# DE-211024_1.net
KiCad netlist of a schematic drawn in Altium Designer
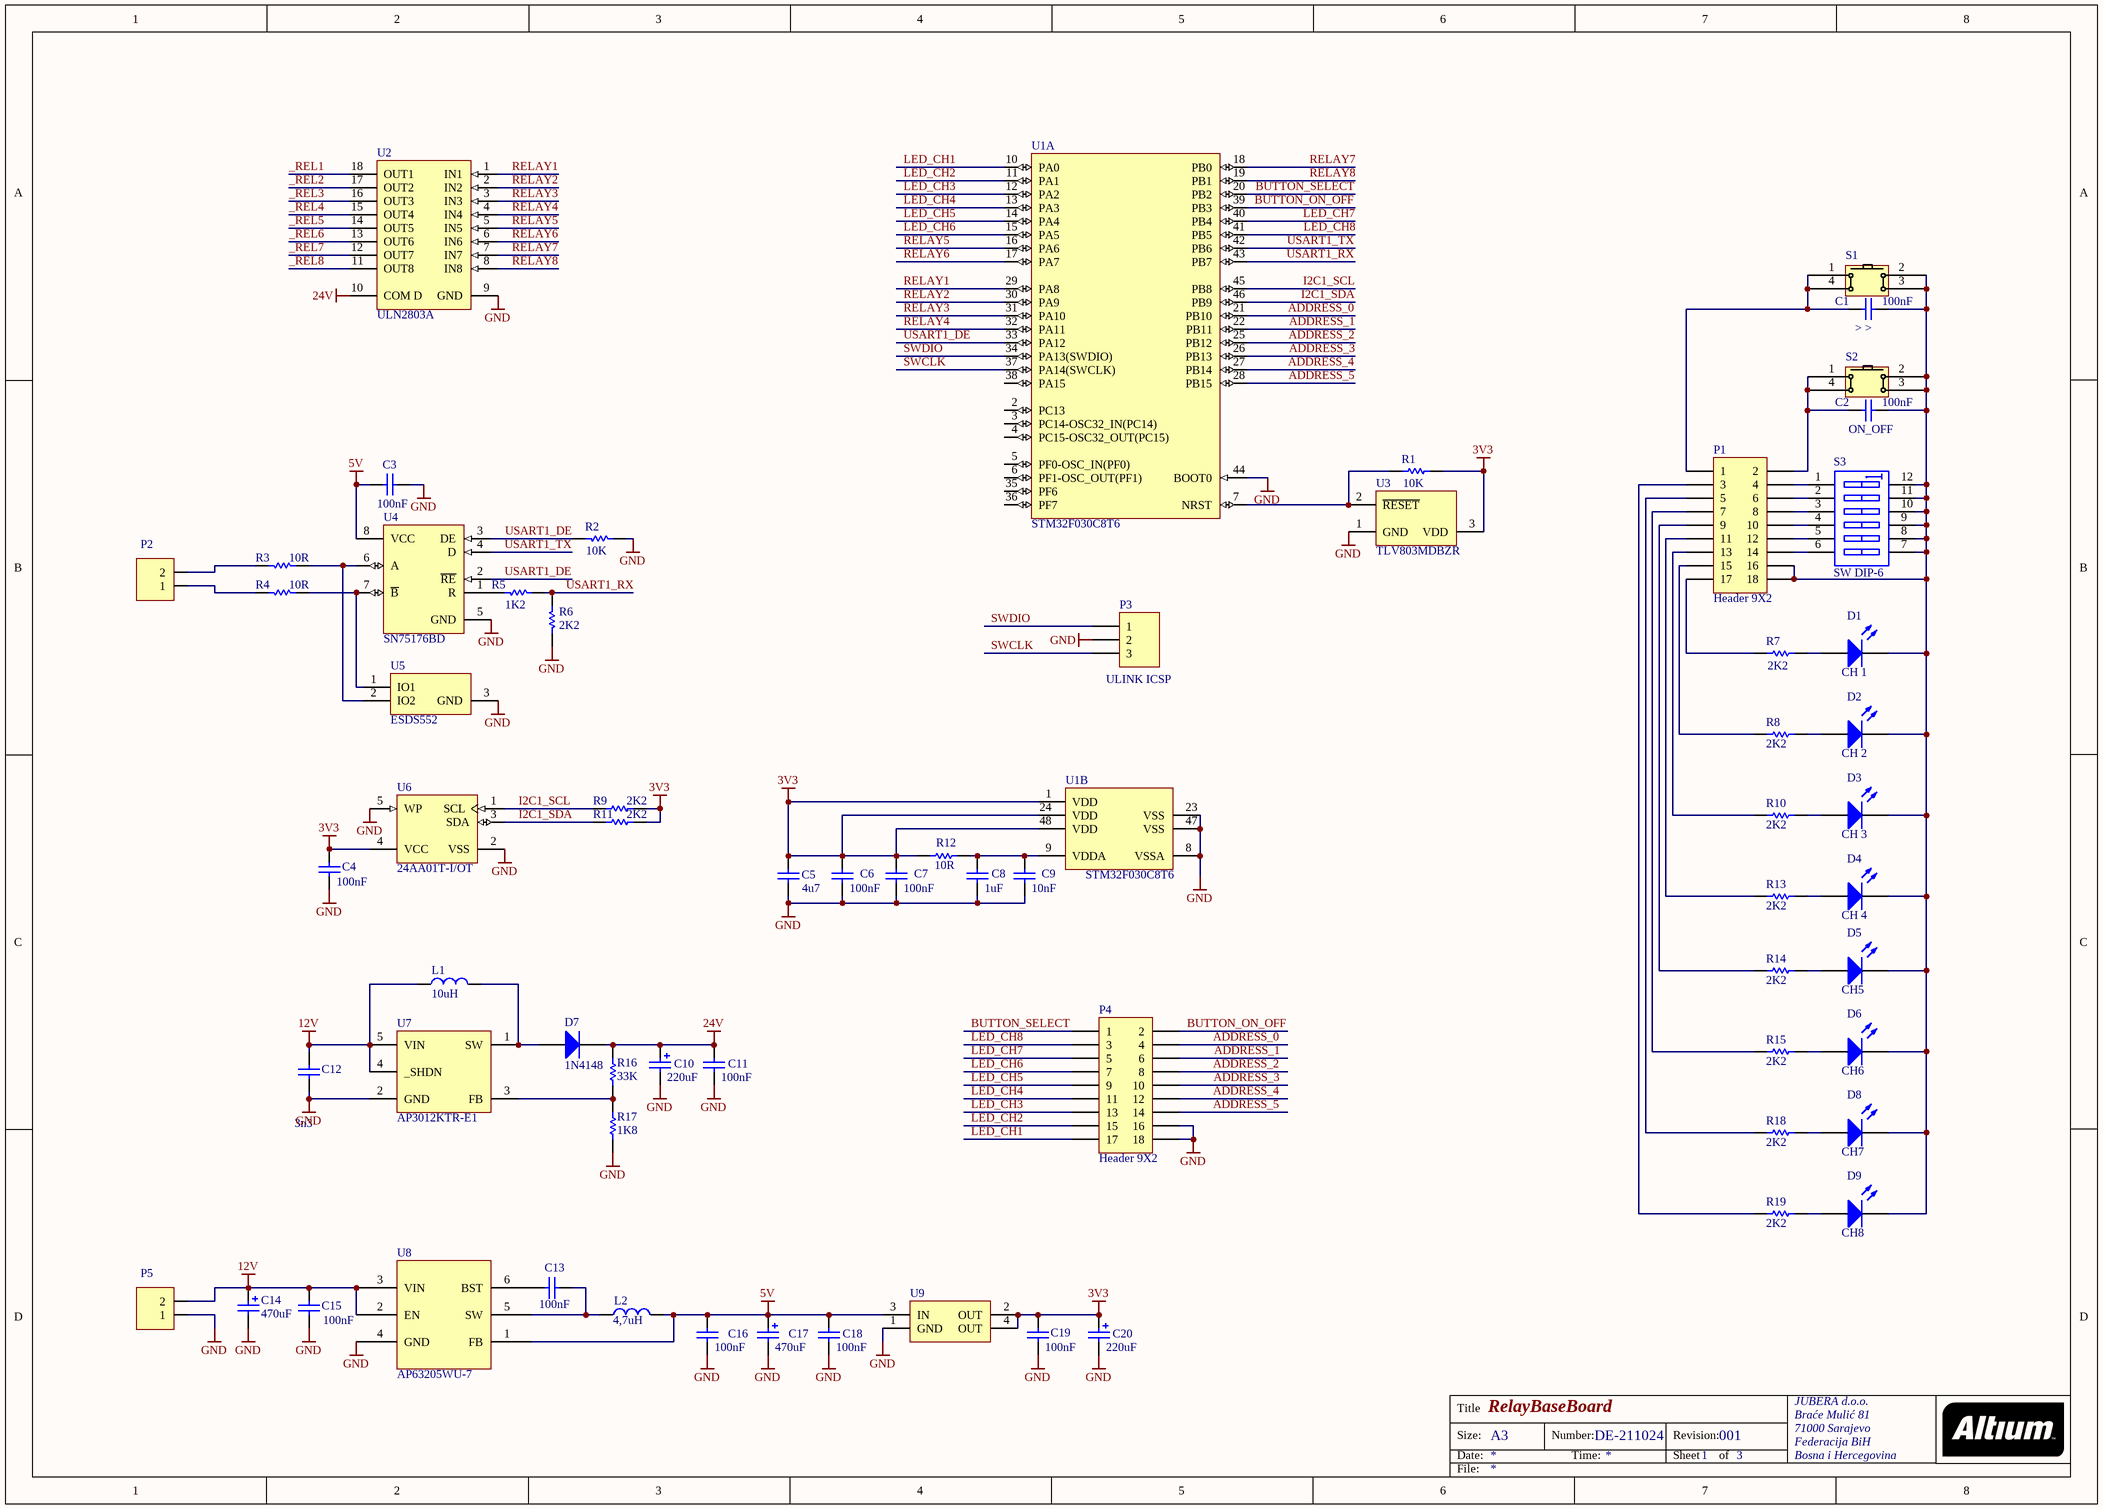
[diagram p0: DE-211024_1.SchDoc]

(export (version "E")
  (design (tool "Eeschema 10.0.6"))
  (components
    (comp (ref "C1")
      (value "100nF")
      (footprint "0603")
      (description "Ceramic Chip Capacitor - Standard")
      (fields (field (name "PUBLISHER") "Altium Limited"))
      (libsource (lib "DE-211024") (part "C0603"))
    )
    (comp (ref "C2")
      (value "100nF")
      (footprint "0603")
      (description "Ceramic Chip Capacitor - Standard")
      (fields (field (name "PUBLISHER") "Altium Limited"))
      (libsource (lib "DE-211024") (part "C0603"))
    )
    (comp (ref "C3")
      (value "100nF")
      (footprint "0603")
      (description "Ceramic Chip Capacitor - Standard")
      (fields (field (name "PUBLISHER") "Altium Limited"))
      (libsource (lib "DE-220817") (part "C0603"))
    )
    (comp (ref "C4")
      (value "100nF")
      (footprint "0603")
      (description "Ceramic Chip Capacitor - Standard")
      (fields (field (name "PUBLISHER") "Altium Limited"))
      (libsource (lib "DE-211024") (part "C0603"))
    )
    (comp (ref "C5")
      (value "4u7")
      (footprint "0805")
      (description "Ceramic Chip Capacitor - Standard")
      (fields (field (name "PUBLISHER") "Altium Limited"))
      (libsource (lib "KEMET Chip Capacitor") (part "C0805"))
    )
    (comp (ref "C6")
      (value "100nF")
      (footprint "0603")
      (description "Ceramic Chip Capacitor - Standard")
      (fields (field (name "PUBLISHER") "Altium Limited"))
      (libsource (lib "KEMET Chip Capacitor") (part "C0603"))
    )
    (comp (ref "C7")
      (value "100nF")
      (footprint "0603")
      (description "Ceramic Chip Capacitor - Standard")
      (fields (field (name "PUBLISHER") "Altium Limited"))
      (libsource (lib "KEMET Chip Capacitor") (part "C0603"))
    )
    (comp (ref "C8")
      (value "1uF")
      (footprint "0603")
      (description "Ceramic Chip Capacitor - Standard")
      (fields (field (name "PUBLISHER") "Altium Limited"))
      (libsource (lib "KEMET Chip Capacitor") (part "C0603"))
    )
    (comp (ref "C9")
      (value "10nF")
      (footprint "0603")
      (description "Ceramic Chip Capacitor - Standard")
      (fields (field (name "PUBLISHER") "Altium Limited"))
      (libsource (lib "KEMET Chip Capacitor") (part "C0603"))
    )
    (comp (ref "C10")
      (value "220uF")
      (footprint "SMD,D8xL10.2mm")
      (description "220uF 35V 195mA@120Hz ±20% SMD,D8xL10.2mm Aluminum Electrolytic Capacitors - SMD ROHS")
      (fields (field (name "PUBLISHER") "Altium Limited"))
      (libsource (lib "DE-211024") (part "ROQANG VT1V221M0810"))
    )
    (comp (ref "C11")
      (value "100nF")
      (footprint "0603")
      (description "Ceramic Chip Capacitor - Standard")
      (fields (field (name "PUBLISHER") "Altium Limited"))
      (libsource (lib "DE-211024") (part "C0603"))
    )
    (comp (ref "C12")
      (value "3n3")
      (footprint "0603")
      (description "Ceramic Chip Capacitor - Standard")
      (fields (field (name "Comment") "C0603") (field (name "PUBLISHER") "Altium Limited"))
      (libsource (lib "DE-211024") (part "C0603"))
    )
    (comp (ref "C13")
      (value "100nF")
      (footprint "0603")
      (description "Ceramic Chip Capacitor - 25V")
      (fields (field (name "PUBLISHER") "Altium Limited"))
      (libsource (lib "DE-211024") (part "C0603"))
    )
    (comp (ref "C14")
      (value "470uF")
      (footprint "ROQANG VT1V471M1010")
      (description "220uF 16V 110mA@120Hz ±20% SMD,D6.3xL7.7mm Aluminum Electrolytic Capacitors - SMD ROHS")
      (fields (field (name "PUBLISHER") "Altium Limited"))
      (libsource (lib "DE-180824") (part "ROQANG VT1C221M0607"))
    )
    (comp (ref "C15")
      (value "100nF")
      (footprint "0603")
      (description "Ceramic Chip Capacitor - Standard")
      (fields (field (name "PUBLISHER") "Altium Limited"))
      (libsource (lib "DE-211024") (part "C0603"))
    )
    (comp (ref "C16")
      (value "100nF")
      (footprint "0603")
      (description "Ceramic Chip Capacitor - 25V")
      (fields (field (name "PUBLISHER") "Altium Limited"))
      (libsource (lib "DE-211024") (part "C0603"))
    )
    (comp (ref "C17")
      (value "470uF")
      (footprint "SMD,D6.3xL7.7mm Aluminum Electrolytic Capacitors")
      (description "220uF 16V 110mA@120Hz ±20% SMD,D6.3xL7.7mm Aluminum Electrolytic Capacitors - SMD ROHS")
      (fields (field (name "PUBLISHER") "Altium Limited"))
      (libsource (lib "DE-180824") (part "ROQANG VT1C221M0607"))
    )
    (comp (ref "C18")
      (value "100nF")
      (footprint "0603")
      (description "Ceramic Chip Capacitor - 25V")
      (fields (field (name "PUBLISHER") "Altium Limited"))
      (libsource (lib "DE-211024") (part "C0603"))
    )
    (comp (ref "C19")
      (value "100nF")
      (footprint "0603")
      (description "Ceramic Chip Capacitor - Standard")
      (fields (field (name "PUBLISHER") "Altium Limited"))
      (libsource (lib "DE-211024") (part "C0603"))
    )
    (comp (ref "C20")
      (value "220uF")
      (footprint "SMD,D6.3xL7.7mm Aluminum Electrolytic Capacitors")
      (description "220uF 16V 110mA@120Hz ±20% SMD,D6.3xL7.7mm Aluminum Electrolytic Capacitors - SMD ROHS")
      (fields (field (name "PUBLISHER") "Altium Limited"))
      (libsource (lib "DE-211024") (part "ROQANG VT1C221M0607"))
    )
    (comp (ref "D1")
      (value "CH 1")
      (footprint "1.6X0.8X0.8")
      (description "High Performance Chip LED, Red")
      (fields (field (name "PUBLISHER") "Altium Limited"))
      (libsource (lib "DE-180824") (part "HSMZ-C190"))
    )
    (comp (ref "D2")
      (value "CH 2")
      (footprint "1.6X0.8X0.8")
      (description "High Performance Chip LED, Red")
      (fields (field (name "PUBLISHER") "Altium Limited"))
      (libsource (lib "DE-180824") (part "HSMZ-C190"))
    )
    (comp (ref "D3")
      (value "CH 3")
      (footprint "1.6X0.8X0.8")
      (description "High Performance Chip LED, Red")
      (fields (field (name "PUBLISHER") "Altium Limited"))
      (libsource (lib "DE-180824") (part "HSMZ-C190"))
    )
    (comp (ref "D4")
      (value "CH 4")
      (footprint "1.6X0.8X0.8")
      (description "High Performance Chip LED, Red")
      (fields (field (name "PUBLISHER") "Altium Limited"))
      (libsource (lib "DE-180824") (part "HSMZ-C190"))
    )
    (comp (ref "D5")
      (value "CH5")
      (footprint "1.6X0.8X0.8")
      (description "High Performance Chip LED, Red")
      (fields (field (name "PUBLISHER") "Altium Limited"))
      (libsource (lib "DE-180824") (part "HSMZ-C190"))
    )
    (comp (ref "D6")
      (value "CH6")
      (footprint "1.6X0.8X0.8")
      (description "High Performance Chip LED, Red")
      (fields (field (name "PUBLISHER") "Altium Limited"))
      (libsource (lib "DE-180824") (part "HSMZ-C190"))
    )
    (comp (ref "D7")
      (value "1N4148")
      (footprint "SOD323")
      (description "General-purpose Diode")
      (fields (field (name "PUBLISHER") "Altium Limited"))
      (libsource (lib "DE-211024") (part "BAS321"))
    )
    (comp (ref "D8")
      (value "CH7")
      (footprint "1.6X0.8X0.8")
      (description "High Performance Chip LED, Red")
      (fields (field (name "PUBLISHER") "Altium Limited"))
      (libsource (lib "DE-180824") (part "HSMZ-C190"))
    )
    (comp (ref "D9")
      (value "CH8")
      (footprint "1.6X0.8X0.8")
      (description "High Performance Chip LED, Red")
      (fields (field (name "PUBLISHER") "Altium Limited"))
      (libsource (lib "DE-180824") (part "HSMZ-C190"))
    )
    (comp (ref "L1")
      (value "10uH")
      (footprint "YJYCOIN CD32YP0302-100M")
      (libsource (lib "DE-211024") (part "Inductor"))
    )
    (comp (ref "L2")
      (value "4,7uH")
      (footprint "XRNR4030-4.7uH/M")
      (description "2A 4.7uH Magnetic Adhesive Inductor ±20% 2.9A SMD-2P,4x4mm Power Inductors ROHS")
      (libsource (lib "DE-211024") (part "Inductor"))
    )
    (comp (ref "P1")
      (value "Header 9X2")
      (footprint "HDR2X9")
      (description "Header, 9-Pin, Dual row")
      (fields (field (name "PUBLISHER") "Altium Limited"))
      (libsource (lib "Miscellaneous Connectors") (part "Header 9X2"))
    )
    (comp (ref "P2")
      (value "~")
      (footprint "TERMINAL BLOK 2")
      (description "Terminal blok konektor 3,5 mm")
      (libsource (lib "DE-211024") (part "TERMINAL BLOK 2"))
    )
    (comp (ref "P3")
      (value "ULINK ICSP")
      (footprint "HDR1X3")
      (description "Header, 3-Pin")
      (fields (field (name "PUBLISHER") "Altium Limited"))
      (libsource (lib "DE-180824") (part "Header 3"))
    )
    (comp (ref "P4")
      (value "Header 9X2")
      (footprint "HDR2X9")
      (description "Header, 9-Pin, Dual row")
      (fields (field (name "PUBLISHER") "Altium Limited"))
      (libsource (lib "Miscellaneous Connectors") (part "Header 9X2"))
    )
    (comp (ref "P5")
      (value "~")
      (footprint "TERMINAL BLOK 2")
      (description "Terminal blok konektor 3,5 mm")
      (libsource (lib "DE-211024") (part "TERMINAL BLOK 2"))
    )
    (comp (ref "R1")
      (value "10K")
      (footprint "ERA-0603")
      (fields (field (name "PUBLISHER") "Altium Limited"))
      (libsource (lib "DE-120824") (part "ERA3Y"))
    )
    (comp (ref "R2")
      (value "10K")
      (footprint "ERA-0603")
      (fields (field (name "PUBLISHER") "Altium Limited"))
      (libsource (lib "DE-220817") (part "ERAV"))
    )
    (comp (ref "R3")
      (value "10R")
      (footprint "ERA-0603")
      (fields (field (name "PUBLISHER") "Altium Limited"))
      (libsource (lib "DE-220817") (part "ERAV"))
    )
    (comp (ref "R4")
      (value "10R")
      (footprint "ERA-0603")
      (fields (field (name "PUBLISHER") "Altium Limited"))
      (libsource (lib "DE-220817") (part "ERAV"))
    )
    (comp (ref "R5")
      (value "1K2")
      (footprint "ERA-0603")
      (fields (field (name "PUBLISHER") "Altium Limited"))
      (libsource (lib "DE-220817") (part "ERAV"))
    )
    (comp (ref "R6")
      (value "2K2")
      (footprint "ERA-0603")
      (fields (field (name "PUBLISHER") "Altium Limited"))
      (libsource (lib "DE-220817") (part "ERAV"))
    )
    (comp (ref "R7")
      (value "2K2")
      (footprint "ERA-0603")
      (fields (field (name "PUBLISHER") "Altium Limited"))
      (libsource (lib "DE-180824") (part "ERA3Y"))
    )
    (comp (ref "R8")
      (value "2K2")
      (footprint "ERA-0603")
      (fields (field (name "PUBLISHER") "Altium Limited"))
      (libsource (lib "DE-180824") (part "ERA3Y"))
    )
    (comp (ref "R9")
      (value "2K2")
      (footprint "ERA-0603")
      (fields (field (name "PUBLISHER") "Altium Limited"))
      (libsource (lib "DE-120824") (part "ERA3Y"))
    )
    (comp (ref "R10")
      (value "2K2")
      (footprint "ERA-0603")
      (fields (field (name "PUBLISHER") "Altium Limited"))
      (libsource (lib "DE-180824") (part "ERA3Y"))
    )
    (comp (ref "R11")
      (value "2K2")
      (footprint "ERA-0603")
      (fields (field (name "PUBLISHER") "Altium Limited"))
      (libsource (lib "DE-120824") (part "ERA3Y"))
    )
    (comp (ref "R12")
      (value "10R")
      (footprint "ERA-0603")
      (fields (field (name "PUBLISHER") "Altium Limited"))
      (libsource (lib "DE-280817") (part "ERA6Y"))
    )
    (comp (ref "R13")
      (value "2K2")
      (footprint "ERA-0603")
      (fields (field (name "PUBLISHER") "Altium Limited"))
      (libsource (lib "DE-180824") (part "ERA3Y"))
    )
    (comp (ref "R14")
      (value "2K2")
      (footprint "ERA-0603")
      (fields (field (name "PUBLISHER") "Altium Limited"))
      (libsource (lib "DE-180824") (part "ERA3Y"))
    )
    (comp (ref "R15")
      (value "2K2")
      (footprint "ERA-0603")
      (fields (field (name "PUBLISHER") "Altium Limited"))
      (libsource (lib "DE-180824") (part "ERA3Y"))
    )
    (comp (ref "R16")
      (value "33K")
      (footprint "ERA-0603")
      (fields (field (name "Comment") "2K2") (field (name "PUBLISHER") "Altium Limited"))
      (libsource (lib "DE-120824") (part "ERA3Y"))
    )
    (comp (ref "R17")
      (value "1K8")
      (footprint "ERA-0603")
      (fields (field (name "Comment") "2K2") (field (name "PUBLISHER") "Altium Limited"))
      (libsource (lib "DE-120824") (part "ERA3Y"))
    )
    (comp (ref "R18")
      (value "2K2")
      (footprint "ERA-0603")
      (fields (field (name "PUBLISHER") "Altium Limited"))
      (libsource (lib "DE-180824") (part "ERA3Y"))
    )
    (comp (ref "R19")
      (value "2K2")
      (footprint "ERA-0603")
      (fields (field (name "PUBLISHER") "Altium Limited"))
      (libsource (lib "DE-180824") (part "ERA3Y"))
    )
    (comp (ref "S1")
      (value "> >")
      (footprint "TACTILE_SWITCH")
      (libsource (lib "DE-180824") (part "TACKTILE_SWITCH"))
    )
    (comp (ref "S2")
      (value "ON_OFF")
      (footprint "TACTILE_SWITCH")
      (libsource (lib "DE-180824") (part "TACKTILE_SWITCH"))
    )
    (comp (ref "S3")
      (value "SW DIP-6")
      (footprint "DIP-12/SW")
      (description "DIP Switch, 6 Position, SPST")
      (fields (field (name "PUBLISHER") "Altium Limited"))
      (libsource (lib "Miscellaneous Devices") (part "SW DIP-6"))
    )
    (comp (ref "U1")
      (value "STM32F030C8T6")
      (footprint "STM-LQFP48_N")
      (libsource (lib "STMicroelectronics STM32 F0") (part "STM32F030C8T6"))
    )
    (comp (ref "U2")
      (value "ULN2803A")
      (footprint "SOIC-18_L11.6-W7.5-P1.27-LS10.3-BL")
      (description "High-Voltage, High-Current Darlington Array")
      (fields (field (name "PUBLISHER") "Altium Limited"))
      (libsource (lib "DE-211024") (part "ULN2803A"))
    )
    (comp (ref "U3")
      (value "TLV803MDBZR")
      (footprint "DBZ3_N")
      (fields (field (name "MANUFACTURER") "Texas Instruments"))
      (libsource (lib "TI Power Management Supervisor and Reset IC") (part "TLV803MDBZR"))
    )
    (comp (ref "U4")
      (value "SN75176BD")
      (footprint "D008_N")
      (description "Differential Bus Transceiver")
      (fields (field (name "PUBLISHER") "Altium Limited"))
      (libsource (lib "DE-010824") (part "SN75176BD"))
    )
    (comp (ref "U5")
      (value "ESDS552")
      (footprint "DCK3_N")
      (fields (field (name "MANUFACTURER") "Texas Instruments") (field (name "PARTNUMBER") "TPD2E007DCKR"))
      (libsource (lib "TI Interface ESD EMI Protection") (part "TPD2E007DCKR"))
    )
    (comp (ref "U6")
      (value "24AA01T-I/OT")
      (footprint "SOT-23-OT5_N")
      (description "1Kbit, 400kHz, 1.8V, I2C Serial EEPROM, 5-Pin SOT-23, Industrial Temperature, Tape and Reel")
      (fields (field (name "PUBLISHER") "Altium Limited"))
      (libsource (lib "Microchip Memory I2C Serial EEPROM") (part "24AA01T-I/OT"))
    )
    (comp (ref "U7")
      (value "AP3012KTR-E1")
      (footprint "SOT-23-5")
      (libsource (lib "DE-211024") (part "AP3012"))
    )
    (comp (ref "U8")
      (value "AP63205WU-7")
      (footprint "TSOT-26")
      (description "2A synchronous  buck converter")
      (libsource (lib "DE-211024") (part "AP63200"))
    )
    (comp (ref "U9")
      (value "~")
      (footprint "ZZ311")
      (description "800mA and 1A Low Dropout Positive Regulator 2.85V, 3.3V, 5V, and Adjustable")
      (fields (field (name "PUBLISHER") "Altium Limited"))
      (libsource (lib "DE-211024") (part "REG1117-3.3"))
    )
  )
  (nets
    (net (code "1") (name "/ADDRESS_0") (class "Default")
      (node (ref "P4") (pin "4") (pinfunction "4_4") (pintype "passive"))
      (node (ref "U1") (pin "21") (pinfunction "PB10_21") (pintype "bidirectional"))
    )
    (net (code "2") (name "/ADDRESS_1") (class "Default")
      (node (ref "P4") (pin "6") (pinfunction "6_6") (pintype "passive"))
      (node (ref "U1") (pin "22") (pinfunction "PB11_22") (pintype "bidirectional"))
    )
    (net (code "3") (name "/ADDRESS_2") (class "Default")
      (node (ref "P4") (pin "8") (pinfunction "8_8") (pintype "passive"))
      (node (ref "U1") (pin "25") (pinfunction "PB12_25") (pintype "bidirectional"))
    )
    (net (code "4") (name "/ADDRESS_3") (class "Default")
      (node (ref "P4") (pin "10") (pinfunction "10_10") (pintype "passive"))
      (node (ref "U1") (pin "26") (pinfunction "PB13_26") (pintype "bidirectional"))
    )
    (net (code "5") (name "/ADDRESS_4") (class "Default")
      (node (ref "P4") (pin "12") (pinfunction "12_12") (pintype "passive"))
      (node (ref "U1") (pin "27") (pinfunction "PB14_27") (pintype "bidirectional"))
    )
    (net (code "6") (name "/ADDRESS_5") (class "Default")
      (node (ref "P4") (pin "14") (pinfunction "14_14") (pintype "passive"))
      (node (ref "U1") (pin "28") (pinfunction "PB15_28") (pintype "bidirectional"))
    )
    (net (code "7") (name "/BUTTON_ON_OFF") (class "Default")
      (node (ref "P4") (pin "2") (pinfunction "2_2") (pintype "passive"))
      (node (ref "U1") (pin "39") (pinfunction "PB3_39") (pintype "bidirectional"))
    )
    (net (code "8") (name "/BUTTON_SELECT") (class "Default")
      (node (ref "P4") (pin "1") (pinfunction "1_1") (pintype "passive"))
      (node (ref "U1") (pin "20") (pinfunction "PB2_20") (pintype "bidirectional"))
    )
    (net (code "9") (name "/I2C1_SCL") (class "Default")
      (node (ref "R9") (pin "1") (pinfunction "1_1") (pintype "passive"))
      (node (ref "U1") (pin "45") (pinfunction "PB8_45") (pintype "bidirectional"))
      (node (ref "U6") (pin "1") (pinfunction "SCL_1") (pintype "input"))
    )
    (net (code "10") (name "/I2C1_SDA") (class "Default")
      (node (ref "R11") (pin "1") (pinfunction "1_1") (pintype "passive"))
      (node (ref "U1") (pin "46") (pinfunction "PB9_46") (pintype "bidirectional"))
      (node (ref "U6") (pin "3") (pinfunction "SDA_3") (pintype "bidirectional"))
    )
    (net (code "11") (name "/LED_CH1") (class "Default")
      (node (ref "P4") (pin "17") (pinfunction "17_17") (pintype "passive"))
      (node (ref "U1") (pin "10") (pinfunction "PA0_10") (pintype "bidirectional"))
    )
    (net (code "12") (name "/LED_CH2") (class "Default")
      (node (ref "P4") (pin "15") (pinfunction "15_15") (pintype "passive"))
      (node (ref "U1") (pin "11") (pinfunction "PA1_11") (pintype "bidirectional"))
    )
    (net (code "13") (name "/LED_CH3") (class "Default")
      (node (ref "P4") (pin "13") (pinfunction "13_13") (pintype "passive"))
      (node (ref "U1") (pin "12") (pinfunction "PA2_12") (pintype "bidirectional"))
    )
    (net (code "14") (name "/LED_CH4") (class "Default")
      (node (ref "P4") (pin "11") (pinfunction "11_11") (pintype "passive"))
      (node (ref "U1") (pin "13") (pinfunction "PA3_13") (pintype "bidirectional"))
    )
    (net (code "15") (name "/LED_CH5") (class "Default")
      (node (ref "P4") (pin "9") (pinfunction "9_9") (pintype "passive"))
      (node (ref "U1") (pin "14") (pinfunction "PA4_14") (pintype "bidirectional"))
    )
    (net (code "16") (name "/LED_CH6") (class "Default")
      (node (ref "P4") (pin "7") (pinfunction "7_7") (pintype "passive"))
      (node (ref "U1") (pin "15") (pinfunction "PA5_15") (pintype "bidirectional"))
    )
    (net (code "17") (name "/LED_CH7") (class "Default")
      (node (ref "P4") (pin "5") (pinfunction "5_5") (pintype "passive"))
      (node (ref "U1") (pin "40") (pinfunction "PB4_40") (pintype "bidirectional"))
    )
    (net (code "18") (name "/LED_CH8") (class "Default")
      (node (ref "P4") (pin "3") (pinfunction "3_3") (pintype "passive"))
      (node (ref "U1") (pin "41") (pinfunction "PB5_41") (pintype "bidirectional"))
    )
    (net (code "19") (name "/RELAY1") (class "Default")
      (node (ref "U1") (pin "29") (pinfunction "PA8_29") (pintype "bidirectional"))
      (node (ref "U2") (pin "1") (pinfunction "IN1_1") (pintype "input"))
    )
    (net (code "20") (name "/RELAY2") (class "Default")
      (node (ref "U1") (pin "30") (pinfunction "PA9_30") (pintype "bidirectional"))
      (node (ref "U2") (pin "2") (pinfunction "IN2_2") (pintype "input"))
    )
    (net (code "21") (name "/RELAY3") (class "Default")
      (node (ref "U1") (pin "31") (pinfunction "PA10_31") (pintype "bidirectional"))
      (node (ref "U2") (pin "3") (pinfunction "IN3_3") (pintype "input"))
    )
    (net (code "22") (name "/RELAY4") (class "Default")
      (node (ref "U1") (pin "32") (pinfunction "PA11_32") (pintype "bidirectional"))
      (node (ref "U2") (pin "4") (pinfunction "IN4_4") (pintype "input"))
    )
    (net (code "23") (name "/RELAY5") (class "Default")
      (node (ref "U1") (pin "16") (pinfunction "PA6_16") (pintype "bidirectional"))
      (node (ref "U2") (pin "5") (pinfunction "IN5_5") (pintype "input"))
    )
    (net (code "24") (name "/RELAY6") (class "Default")
      (node (ref "U1") (pin "17") (pinfunction "PA7_17") (pintype "bidirectional"))
      (node (ref "U2") (pin "6") (pinfunction "IN6_6") (pintype "input"))
    )
    (net (code "25") (name "/RELAY7") (class "Default")
      (node (ref "U1") (pin "18") (pinfunction "PB0_18") (pintype "bidirectional"))
      (node (ref "U2") (pin "7") (pinfunction "IN7_7") (pintype "input"))
    )
    (net (code "26") (name "/RELAY8") (class "Default")
      (node (ref "U1") (pin "19") (pinfunction "PB1_19") (pintype "bidirectional"))
      (node (ref "U2") (pin "8") (pinfunction "IN8_8") (pintype "input"))
    )
    (net (code "27") (name "/SWCLK") (class "Default")
      (node (ref "P3") (pin "3") (pinfunction "3_3") (pintype "passive"))
      (node (ref "U1") (pin "37") (pinfunction "PA14(SWCLK)_37") (pintype "bidirectional"))
    )
    (net (code "28") (name "/SWDIO") (class "Default")
      (node (ref "P3") (pin "1") (pinfunction "1_1") (pintype "passive"))
      (node (ref "U1") (pin "34") (pinfunction "PA13(SWDIO)_34") (pintype "bidirectional"))
    )
    (net (code "29") (name "/USART1_DE") (class "Default")
      (node (ref "R2") (pin "2") (pinfunction "2_2") (pintype "passive"))
      (node (ref "U1") (pin "33") (pinfunction "PA12_33") (pintype "bidirectional"))
      (node (ref "U4") (pin "2") (pinfunction "~{RE}_2") (pintype "input"))
      (node (ref "U4") (pin "3") (pinfunction "DE_3") (pintype "input"))
    )
    (net (code "30") (name "/USART1_RX") (class "Default")
      (node (ref "R5") (pin "1") (pinfunction "1_1") (pintype "passive"))
      (node (ref "R6") (pin "1") (pinfunction "1_1") (pintype "passive"))
      (node (ref "U1") (pin "43") (pinfunction "PB7_43") (pintype "bidirectional"))
    )
    (net (code "31") (name "/USART1_TX") (class "Default")
      (node (ref "U1") (pin "42") (pinfunction "PB6_42") (pintype "bidirectional"))
      (node (ref "U4") (pin "4") (pinfunction "D_4") (pintype "input"))
    )
    (net (code "32") (name "/_REL1") (class "Default")
      (node (ref "U2") (pin "18") (pinfunction "OUT1_18") (pintype "open_collector"))
    )
    (net (code "33") (name "/_REL2") (class "Default")
      (node (ref "U2") (pin "17") (pinfunction "OUT2_17") (pintype "open_collector"))
    )
    (net (code "34") (name "/_REL3") (class "Default")
      (node (ref "U2") (pin "16") (pinfunction "OUT3_16") (pintype "open_collector"))
    )
    (net (code "35") (name "/_REL4") (class "Default")
      (node (ref "U2") (pin "15") (pinfunction "OUT4_15") (pintype "open_collector"))
    )
    (net (code "36") (name "/_REL5") (class "Default")
      (node (ref "U2") (pin "14") (pinfunction "OUT5_14") (pintype "open_collector"))
    )
    (net (code "37") (name "/_REL6") (class "Default")
      (node (ref "U2") (pin "13") (pinfunction "OUT6_13") (pintype "open_collector"))
    )
    (net (code "38") (name "/_REL7") (class "Default")
      (node (ref "U2") (pin "12") (pinfunction "OUT7_12") (pintype "open_collector"))
    )
    (net (code "39") (name "/_REL8") (class "Default")
      (node (ref "U2") (pin "11") (pinfunction "OUT8_11") (pintype "open_collector"))
    )
    (net (code "40") (name "3V3") (class "Default")
      (node (ref "C19") (pin "2") (pinfunction "2_2") (pintype "passive"))
      (node (ref "C20") (pin "1") (pinfunction "1_1") (pintype "passive"))
      (node (ref "C4") (pin "2") (pinfunction "2_2") (pintype "passive"))
      (node (ref "C5") (pin "1") (pinfunction "1_1") (pintype "passive"))
      (node (ref "C6") (pin "1") (pinfunction "1_1") (pintype "passive"))
      (node (ref "C7") (pin "1") (pinfunction "1_1") (pintype "passive"))
      (node (ref "R1") (pin "2") (pinfunction "2_2") (pintype "passive"))
      (node (ref "R11") (pin "2") (pinfunction "2_2") (pintype "passive"))
      (node (ref "R12") (pin "2") (pinfunction "2_2") (pintype "passive"))
      (node (ref "R9") (pin "2") (pinfunction "2_2") (pintype "passive"))
      (node (ref "U1") (pin "1") (pinfunction "VDD_1") (pintype "power_in"))
      (node (ref "U1") (pin "24") (pinfunction "VDD_24") (pintype "power_in"))
      (node (ref "U1") (pin "48") (pinfunction "VDD_48") (pintype "power_in"))
      (node (ref "U3") (pin "3") (pinfunction "VDD_3") (pintype "power_in"))
      (node (ref "U6") (pin "4") (pinfunction "VCC_4") (pintype "power_in"))
      (node (ref "U9") (pin "2") (pinfunction "OUT_2") (pintype "power_in"))
      (node (ref "U9") (pin "4") (pinfunction "OUT_4") (pintype "power_in"))
    )
    (net (code "41") (name "5V") (class "Default")
      (node (ref "C16") (pin "2") (pinfunction "2_2") (pintype "passive"))
      (node (ref "C17") (pin "1") (pinfunction "1_1") (pintype "passive"))
      (node (ref "C18") (pin "2") (pinfunction "2_2") (pintype "passive"))
      (node (ref "C3") (pin "1") (pinfunction "1_1") (pintype "passive"))
      (node (ref "L2") (pin "1") (pinfunction "1_1") (pintype "passive"))
      (node (ref "U4") (pin "8") (pinfunction "VCC_8") (pintype "power_in"))
      (node (ref "U8") (pin "1") (pinfunction "FB_1") (pintype "passive"))
      (node (ref "U9") (pin "3") (pinfunction "IN_3") (pintype "power_in"))
    )
    (net (code "42") (name "12V") (class "Default")
      (node (ref "C12") (pin "2") (pinfunction "2_2") (pintype "passive"))
      (node (ref "C14") (pin "1") (pinfunction "1_1") (pintype "passive"))
      (node (ref "C15") (pin "2") (pinfunction "2_2") (pintype "passive"))
      (node (ref "L1") (pin "2") (pinfunction "2_2") (pintype "passive"))
      (node (ref "P5") (pin "2") (pinfunction "2_2") (pintype "passive"))
      (node (ref "U7") (pin "4") (pinfunction "_SHDN_4") (pintype "passive"))
      (node (ref "U7") (pin "5") (pinfunction "VIN_5") (pintype "power_in"))
      (node (ref "U8") (pin "2") (pinfunction "EN_2") (pintype "passive"))
      (node (ref "U8") (pin "3") (pinfunction "VIN_3") (pintype "power_in"))
    )
    (net (code "43") (name "24V") (class "Default")
      (node (ref "C10") (pin "1") (pinfunction "1_1") (pintype "passive"))
      (node (ref "C11") (pin "2") (pinfunction "2_2") (pintype "passive"))
      (node (ref "D7") (pin "1") (pinfunction "K_1") (pintype "passive"))
      (node (ref "R16") (pin "2") (pinfunction "2_2") (pintype "passive"))
      (node (ref "U2") (pin "10") (pinfunction "COM_D_10") (pintype "passive"))
    )
    (net (code "44") (name "GND") (class "Default")
      (node (ref "C10") (pin "2") (pinfunction "2_2") (pintype "passive"))
      (node (ref "C11") (pin "1") (pinfunction "1_1") (pintype "passive"))
      (node (ref "C12") (pin "1") (pinfunction "1_1") (pintype "passive"))
      (node (ref "C14") (pin "2") (pinfunction "2_2") (pintype "passive"))
      (node (ref "C15") (pin "1") (pinfunction "1_1") (pintype "passive"))
      (node (ref "C16") (pin "1") (pinfunction "1_1") (pintype "passive"))
      (node (ref "C17") (pin "2") (pinfunction "2_2") (pintype "passive"))
      (node (ref "C18") (pin "1") (pinfunction "1_1") (pintype "passive"))
      (node (ref "C19") (pin "1") (pinfunction "1_1") (pintype "passive"))
      (node (ref "C20") (pin "2") (pinfunction "2_2") (pintype "passive"))
      (node (ref "C3") (pin "2") (pinfunction "2_2") (pintype "passive"))
      (node (ref "C4") (pin "1") (pinfunction "1_1") (pintype "passive"))
      (node (ref "C5") (pin "2") (pinfunction "2_2") (pintype "passive"))
      (node (ref "C6") (pin "2") (pinfunction "2_2") (pintype "passive"))
      (node (ref "C7") (pin "2") (pinfunction "2_2") (pintype "passive"))
      (node (ref "C8") (pin "2") (pinfunction "2_2") (pintype "passive"))
      (node (ref "C9") (pin "2") (pinfunction "2_2") (pintype "passive"))
      (node (ref "P3") (pin "2") (pinfunction "2_2") (pintype "passive"))
      (node (ref "P4") (pin "16") (pinfunction "16_16") (pintype "passive"))
      (node (ref "P4") (pin "18") (pinfunction "18_18") (pintype "passive"))
      (node (ref "P5") (pin "1") (pinfunction "1_1") (pintype "passive"))
      (node (ref "R17") (pin "1") (pinfunction "1_1") (pintype "passive"))
      (node (ref "R2") (pin "1") (pinfunction "1_1") (pintype "passive"))
      (node (ref "R6") (pin "2") (pinfunction "2_2") (pintype "passive"))
      (node (ref "U1") (pin "23") (pinfunction "VSS_23") (pintype "power_in"))
      (node (ref "U1") (pin "44") (pinfunction "BOOT0_44") (pintype "input"))
      (node (ref "U1") (pin "47") (pinfunction "VSS_47") (pintype "power_in"))
      (node (ref "U1") (pin "8") (pinfunction "VSSA_8") (pintype "power_in"))
      (node (ref "U2") (pin "9") (pinfunction "GND_9") (pintype "power_in"))
      (node (ref "U3") (pin "1") (pinfunction "GND_1") (pintype "power_in"))
      (node (ref "U4") (pin "5") (pinfunction "GND_5") (pintype "power_in"))
      (node (ref "U5") (pin "3") (pinfunction "GND_3") (pintype "power_in"))
      (node (ref "U6") (pin "2") (pinfunction "VSS_2") (pintype "power_in"))
      (node (ref "U6") (pin "5") (pinfunction "WP_5") (pintype "input"))
      (node (ref "U7") (pin "2") (pinfunction "GND_2") (pintype "power_in"))
      (node (ref "U8") (pin "4") (pinfunction "GND_4") (pintype "power_in"))
      (node (ref "U9") (pin "1") (pinfunction "GND_1") (pintype "power_in"))
    )
    (net (code "45") (name "Net-(C1-Pad1)") (class "Default")
      (node (ref "C1") (pin "1") (pinfunction "1_1") (pintype "passive"))
      (node (ref "P1") (pin "1") (pinfunction "1_1") (pintype "passive"))
      (node (ref "S1") (pin "1") (pinfunction "1_1") (pintype "passive"))
      (node (ref "S1") (pin "4") (pinfunction "4_4") (pintype "passive"))
    )
    (net (code "46") (name "Net-(C2-Pad1)") (class "Default")
      (node (ref "C2") (pin "1") (pinfunction "1_1") (pintype "passive"))
      (node (ref "P1") (pin "2") (pinfunction "2_2") (pintype "passive"))
      (node (ref "S2") (pin "1") (pinfunction "1_1") (pintype "passive"))
      (node (ref "S2") (pin "4") (pinfunction "4_4") (pintype "passive"))
    )
    (net (code "47") (name "Net-(D1-A)") (class "Default")
      (node (ref "D1") (pin "1") (pinfunction "A_1") (pintype "passive"))
      (node (ref "R7") (pin "2") (pinfunction "2_2") (pintype "passive"))
    )
    (net (code "48") (name "Net-(D1-K)") (class "Default")
      (node (ref "C1") (pin "2") (pinfunction "2_2") (pintype "passive"))
      (node (ref "C2") (pin "2") (pinfunction "2_2") (pintype "passive"))
      (node (ref "D1") (pin "2") (pinfunction "K_2") (pintype "passive"))
      (node (ref "D2") (pin "2") (pinfunction "K_2") (pintype "passive"))
      (node (ref "D3") (pin "2") (pinfunction "K_2") (pintype "passive"))
      (node (ref "D4") (pin "2") (pinfunction "K_2") (pintype "passive"))
      (node (ref "D5") (pin "2") (pinfunction "K_2") (pintype "passive"))
      (node (ref "D6") (pin "2") (pinfunction "K_2") (pintype "passive"))
      (node (ref "D8") (pin "2") (pinfunction "K_2") (pintype "passive"))
      (node (ref "D9") (pin "2") (pinfunction "K_2") (pintype "passive"))
      (node (ref "P1") (pin "16") (pinfunction "16_16") (pintype "passive"))
      (node (ref "P1") (pin "18") (pinfunction "18_18") (pintype "passive"))
      (node (ref "S1") (pin "2") (pinfunction "2_2") (pintype "passive"))
      (node (ref "S1") (pin "3") (pinfunction "3_3") (pintype "passive"))
      (node (ref "S2") (pin "2") (pinfunction "2_2") (pintype "passive"))
      (node (ref "S2") (pin "3") (pinfunction "3_3") (pintype "passive"))
      (node (ref "S3") (pin "10") (pinfunction "B3_10") (pintype "passive"))
      (node (ref "S3") (pin "11") (pinfunction "B2_11") (pintype "passive"))
      (node (ref "S3") (pin "12") (pinfunction "B1_12") (pintype "passive"))
      (node (ref "S3") (pin "7") (pinfunction "B6_7") (pintype "passive"))
      (node (ref "S3") (pin "8") (pinfunction "B5_8") (pintype "passive"))
      (node (ref "S3") (pin "9") (pinfunction "B4_9") (pintype "passive"))
    )
    (net (code "49") (name "Net-(D2-A)") (class "Default")
      (node (ref "D2") (pin "1") (pinfunction "A_1") (pintype "passive"))
      (node (ref "R8") (pin "2") (pinfunction "2_2") (pintype "passive"))
    )
    (net (code "50") (name "Net-(D3-A)") (class "Default")
      (node (ref "D3") (pin "1") (pinfunction "A_1") (pintype "passive"))
      (node (ref "R10") (pin "2") (pinfunction "2_2") (pintype "passive"))
    )
    (net (code "51") (name "Net-(D4-A)") (class "Default")
      (node (ref "D4") (pin "1") (pinfunction "A_1") (pintype "passive"))
      (node (ref "R13") (pin "2") (pinfunction "2_2") (pintype "passive"))
    )
    (net (code "52") (name "Net-(D5-A)") (class "Default")
      (node (ref "D5") (pin "1") (pinfunction "A_1") (pintype "passive"))
      (node (ref "R14") (pin "2") (pinfunction "2_2") (pintype "passive"))
    )
    (net (code "53") (name "Net-(D6-A)") (class "Default")
      (node (ref "D6") (pin "1") (pinfunction "A_1") (pintype "passive"))
      (node (ref "R15") (pin "2") (pinfunction "2_2") (pintype "passive"))
    )
    (net (code "54") (name "Net-(D7-A)") (class "Default")
      (node (ref "D7") (pin "2") (pinfunction "A_2") (pintype "passive"))
      (node (ref "L1") (pin "1") (pinfunction "1_1") (pintype "passive"))
      (node (ref "U7") (pin "1") (pinfunction "SW_1") (pintype "passive"))
    )
    (net (code "55") (name "Net-(D8-A)") (class "Default")
      (node (ref "D8") (pin "1") (pinfunction "A_1") (pintype "passive"))
      (node (ref "R18") (pin "2") (pinfunction "2_2") (pintype "passive"))
    )
    (net (code "56") (name "Net-(D9-A)") (class "Default")
      (node (ref "D9") (pin "1") (pinfunction "A_1") (pintype "passive"))
      (node (ref "R19") (pin "2") (pinfunction "2_2") (pintype "passive"))
    )
    (net (code "57") (name "Net-(P1-Pad3)") (class "Default")
      (node (ref "P1") (pin "3") (pinfunction "3_3") (pintype "passive"))
      (node (ref "R19") (pin "1") (pinfunction "1_1") (pintype "passive"))
    )
    (net (code "58") (name "Net-(P1-Pad5)") (class "Default")
      (node (ref "P1") (pin "5") (pinfunction "5_5") (pintype "passive"))
      (node (ref "R18") (pin "1") (pinfunction "1_1") (pintype "passive"))
    )
    (net (code "59") (name "Net-(P1-Pad7)") (class "Default")
      (node (ref "P1") (pin "7") (pinfunction "7_7") (pintype "passive"))
      (node (ref "R15") (pin "1") (pinfunction "1_1") (pintype "passive"))
    )
    (net (code "60") (name "Net-(P1-Pad9)") (class "Default")
      (node (ref "P1") (pin "9") (pinfunction "9_9") (pintype "passive"))
      (node (ref "R14") (pin "1") (pinfunction "1_1") (pintype "passive"))
    )
    (net (code "61") (name "Net-(P1-Pad11)") (class "Default")
      (node (ref "P1") (pin "11") (pinfunction "11_11") (pintype "passive"))
      (node (ref "R13") (pin "1") (pinfunction "1_1") (pintype "passive"))
    )
    (net (code "62") (name "Net-(P1-Pad13)") (class "Default")
      (node (ref "P1") (pin "13") (pinfunction "13_13") (pintype "passive"))
      (node (ref "R10") (pin "1") (pinfunction "1_1") (pintype "passive"))
    )
    (net (code "63") (name "Net-(P1-Pad15)") (class "Default")
      (node (ref "P1") (pin "15") (pinfunction "15_15") (pintype "passive"))
      (node (ref "R8") (pin "1") (pinfunction "1_1") (pintype "passive"))
    )
    (net (code "64") (name "Net-(P1-Pad17)") (class "Default")
      (node (ref "P1") (pin "17") (pinfunction "17_17") (pintype "passive"))
      (node (ref "R7") (pin "1") (pinfunction "1_1") (pintype "passive"))
    )
    (net (code "65") (name "Net-(P2-Pad1)") (class "Default")
      (node (ref "P2") (pin "1") (pinfunction "1_1") (pintype "passive"))
      (node (ref "R4") (pin "1") (pinfunction "1_1") (pintype "passive"))
    )
    (net (code "66") (name "Net-(P2-Pad2)") (class "Default")
      (node (ref "P2") (pin "2") (pinfunction "2_2") (pintype "passive"))
      (node (ref "R3") (pin "1") (pinfunction "1_1") (pintype "passive"))
    )
    (net (code "67") (name "Net-(S3-A1)") (class "Default")
      (node (ref "P1") (pin "4") (pinfunction "4_4") (pintype "passive"))
      (node (ref "S3") (pin "1") (pinfunction "A1_1") (pintype "passive"))
    )
    (net (code "68") (name "Net-(S3-A2)") (class "Default")
      (node (ref "P1") (pin "6") (pinfunction "6_6") (pintype "passive"))
      (node (ref "S3") (pin "2") (pinfunction "A2_2") (pintype "passive"))
    )
    (net (code "69") (name "Net-(S3-A3)") (class "Default")
      (node (ref "P1") (pin "8") (pinfunction "8_8") (pintype "passive"))
      (node (ref "S3") (pin "3") (pinfunction "A3_3") (pintype "passive"))
    )
    (net (code "70") (name "Net-(S3-A4)") (class "Default")
      (node (ref "P1") (pin "10") (pinfunction "10_10") (pintype "passive"))
      (node (ref "S3") (pin "4") (pinfunction "A4_4") (pintype "passive"))
    )
    (net (code "71") (name "Net-(S3-A5)") (class "Default")
      (node (ref "P1") (pin "12") (pinfunction "12_12") (pintype "passive"))
      (node (ref "S3") (pin "5") (pinfunction "A5_5") (pintype "passive"))
    )
    (net (code "72") (name "Net-(S3-A6)") (class "Default")
      (node (ref "P1") (pin "14") (pinfunction "14_14") (pintype "passive"))
      (node (ref "S3") (pin "6") (pinfunction "A6_6") (pintype "passive"))
    )
    (net (code "73") (name "Net-(U1A-NRST)") (class "Default")
      (node (ref "R1") (pin "1") (pinfunction "1_1") (pintype "passive"))
      (node (ref "U1") (pin "7") (pinfunction "NRST_7") (pintype "bidirectional"))
      (node (ref "U3") (pin "2") (pinfunction "~{RESET}_2") (pintype "open_collector"))
    )
    (net (code "74") (name "Net-(U1B-VDDA)") (class "Default")
      (node (ref "C8") (pin "1") (pinfunction "1_1") (pintype "passive"))
      (node (ref "C9") (pin "1") (pinfunction "1_1") (pintype "passive"))
      (node (ref "R12") (pin "1") (pinfunction "1_1") (pintype "passive"))
      (node (ref "U1") (pin "9") (pinfunction "VDDA_9") (pintype "power_in"))
    )
    (net (code "75") (name "Net-(U4-A)") (class "Default")
      (node (ref "R3") (pin "2") (pinfunction "2_2") (pintype "passive"))
      (node (ref "U4") (pin "6") (pinfunction "A_6") (pintype "bidirectional"))
      (node (ref "U5") (pin "2") (pinfunction "IO2_2") (pintype "passive"))
    )
    (net (code "76") (name "Net-(U4-R)") (class "Default")
      (node (ref "R5") (pin "2") (pinfunction "2_2") (pintype "passive"))
      (node (ref "U4") (pin "1") (pinfunction "R_1") (pintype "tri_state"))
    )
    (net (code "77") (name "Net-(U4-~{B})") (class "Default")
      (node (ref "R4") (pin "2") (pinfunction "2_2") (pintype "passive"))
      (node (ref "U4") (pin "7") (pinfunction "~{B}_7") (pintype "bidirectional"))
      (node (ref "U5") (pin "1") (pinfunction "IO1_1") (pintype "passive"))
    )
    (net (code "78") (name "Net-(U7-FB)") (class "Default")
      (node (ref "R16") (pin "1") (pinfunction "1_1") (pintype "passive"))
      (node (ref "R17") (pin "2") (pinfunction "2_2") (pintype "passive"))
      (node (ref "U7") (pin "3") (pinfunction "FB_3") (pintype "passive"))
    )
    (net (code "79") (name "Net-(U8-BST)") (class "Default")
      (node (ref "C13") (pin "2") (pinfunction "2_2") (pintype "passive"))
      (node (ref "U8") (pin "6") (pinfunction "BST_6") (pintype "passive"))
    )
    (net (code "80") (name "Net-(U8-SW)") (class "Default")
      (node (ref "C13") (pin "1") (pinfunction "1_1") (pintype "passive"))
      (node (ref "L2") (pin "2") (pinfunction "2_2") (pintype "passive"))
      (node (ref "U8") (pin "5") (pinfunction "SW_5") (pintype "passive"))
    )
    (net (code "81") (name "unconnected-(U1A-PA15-Pad38)") (class "Default")
      (node (ref "U1") (pin "38") (pinfunction "PA15_38") (pintype "bidirectional"))
    )
    (net (code "82") (name "unconnected-(U1A-PC13-Pad2)") (class "Default")
      (node (ref "U1") (pin "2") (pinfunction "PC13_2") (pintype "bidirectional"))
    )
    (net (code "83") (name "unconnected-(U1A-PC14-OSC32_IN(PC14)-Pad3)") (class "Default")
      (node (ref "U1") (pin "3") (pinfunction "PC14-OSC32_IN(PC14)_3") (pintype "bidirectional"))
    )
    (net (code "84") (name "unconnected-(U1A-PC15-OSC32_OUT(PC15)-Pad4)") (class "Default")
      (node (ref "U1") (pin "4") (pinfunction "PC15-OSC32_OUT(PC15)_4") (pintype "bidirectional"))
    )
    (net (code "85") (name "unconnected-(U1A-PF0-OSC_IN(PF0)-Pad5)") (class "Default")
      (node (ref "U1") (pin "5") (pinfunction "PF0-OSC_IN(PF0)_5") (pintype "bidirectional"))
    )
    (net (code "86") (name "unconnected-(U1A-PF1-OSC_OUT(PF1)-Pad6)") (class "Default")
      (node (ref "U1") (pin "6") (pinfunction "PF1-OSC_OUT(PF1)_6") (pintype "bidirectional"))
    )
    (net (code "87") (name "unconnected-(U1A-PF6-Pad35)") (class "Default")
      (node (ref "U1") (pin "35") (pinfunction "PF6_35") (pintype "bidirectional"))
    )
    (net (code "88") (name "unconnected-(U1A-PF7-Pad36)") (class "Default")
      (node (ref "U1") (pin "36") (pinfunction "PF7_36") (pintype "bidirectional"))
    )
  )
)
